# Schema_Arduino_Blinky.net
KiCad netlist of a schematic drawn in EAGLE
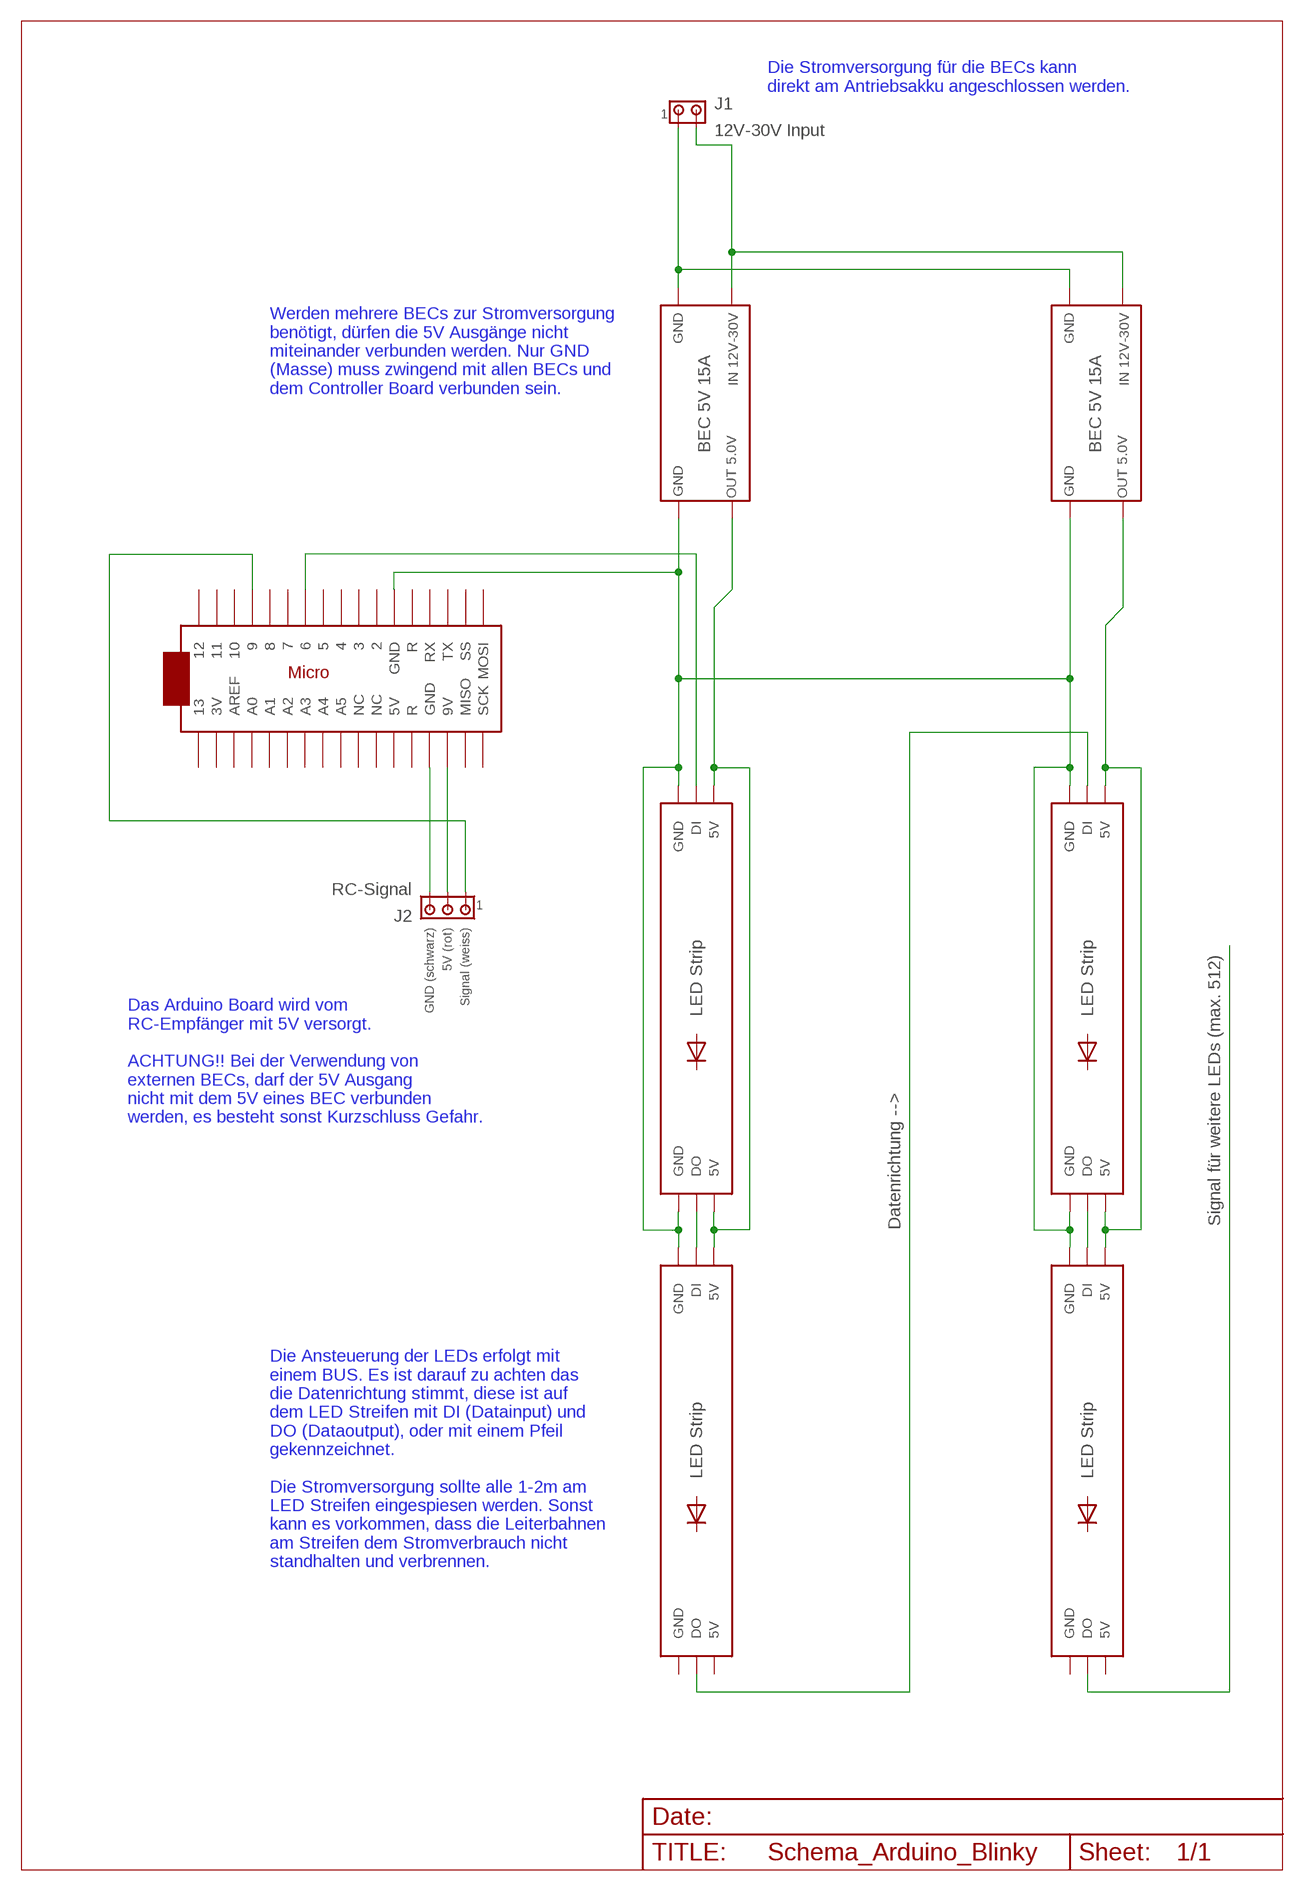
[diagram p0: schematic, sheet 1]

(export (version "E")
  (design (tool "Eeschema 10.0.6"))
  (components
    (comp (ref "J1")
      (value "12V-30V Input")
      (footprint "eagle-import:350428-1")
      (libsource (lib "eagle-import") (part "350428-1"))
    )
    (comp (ref "J2")
      (value "RC-Signal")
      (footprint "eagle-import:350429-1")
      (libsource (lib "eagle-import") (part "350429-1"))
    )
    (comp (ref "U$1")
      (value "ARDUINOMICRO")
      (footprint "eagle-import:ARDUINOMICRO")
      (libsource (lib "eagle-import") (part "ARDUINOMICRO"))
    )
  )
  (nets
    (net (code "1") (name "Net-(J2-Pad3)") (class "Default")
      (node (ref "J2") (pin "3") (pinfunction "3_3") (pintype "passive"))
      (node (ref "U$1") (pin "P$12") (pinfunction "GND_P$12") (pintype "bidirectional"))
    )
    (net (code "2") (name "Net-(U$1-9)") (class "Default")
      (node (ref "J2") (pin "1") (pinfunction "1_1") (pintype "passive"))
      (node (ref "U$1") (pin "P$4") (pinfunction "9_P$4") (pintype "bidirectional"))
    )
    (net (code "3") (name "Net-(U$1-9V)") (class "Default")
      (node (ref "J2") (pin "2") (pinfunction "2_2") (pintype "passive"))
      (node (ref "U$1") (pin "P$20") (pinfunction "9V_P$20") (pintype "bidirectional"))
    )
    (net (code "4") (name "unconnected-(J1-Pad1)") (class "Default")
      (node (ref "J1") (pin "1") (pinfunction "1_1") (pintype "passive"))
    )
    (net (code "5") (name "unconnected-(J1-Pad2)") (class "Default")
      (node (ref "J1") (pin "2") (pinfunction "2_2") (pintype "passive"))
    )
    (net (code "6") (name "unconnected-(U$1-2-PadP$11)") (class "Default")
      (node (ref "U$1") (pin "P$11") (pinfunction "2_P$11") (pintype "bidirectional"))
    )
    (net (code "7") (name "unconnected-(U$1-3-PadP$10)") (class "Default")
      (node (ref "U$1") (pin "P$10") (pinfunction "3_P$10") (pintype "bidirectional"))
    )
    (net (code "8") (name "unconnected-(U$1-3V-PadP$33)") (class "Default")
      (node (ref "U$1") (pin "P$33") (pinfunction "3V_P$33") (pintype "bidirectional"))
    )
    (net (code "9") (name "unconnected-(U$1-4-PadP$9)") (class "Default")
      (node (ref "U$1") (pin "P$9") (pinfunction "4_P$9") (pintype "bidirectional"))
    )
    (net (code "10") (name "unconnected-(U$1-5-PadP$8)") (class "Default")
      (node (ref "U$1") (pin "P$8") (pinfunction "5_P$8") (pintype "bidirectional"))
    )
    (net (code "11") (name "unconnected-(U$1-5V-PadP$23)") (class "Default")
      (node (ref "U$1") (pin "P$23") (pinfunction "5V_P$23") (pintype "bidirectional"))
    )
    (net (code "12") (name "unconnected-(U$1-6-PadP$7)") (class "Default")
      (node (ref "U$1") (pin "P$7") (pinfunction "6_P$7") (pintype "bidirectional"))
    )
    (net (code "13") (name "unconnected-(U$1-7-PadP$6)") (class "Default")
      (node (ref "U$1") (pin "P$6") (pinfunction "7_P$6") (pintype "bidirectional"))
    )
    (net (code "14") (name "unconnected-(U$1-8-PadP$5)") (class "Default")
      (node (ref "U$1") (pin "P$5") (pinfunction "8_P$5") (pintype "bidirectional"))
    )
    (net (code "15") (name "unconnected-(U$1-10-PadP$3)") (class "Default")
      (node (ref "U$1") (pin "P$3") (pinfunction "10_P$3") (pintype "bidirectional"))
    )
    (net (code "16") (name "unconnected-(U$1-11-PadP$2)") (class "Default")
      (node (ref "U$1") (pin "P$2") (pinfunction "11_P$2") (pintype "bidirectional"))
    )
    (net (code "17") (name "unconnected-(U$1-12-PadP$1)") (class "Default")
      (node (ref "U$1") (pin "P$1") (pinfunction "12_P$1") (pintype "bidirectional"))
    )
    (net (code "18") (name "unconnected-(U$1-13-PadP$34)") (class "Default")
      (node (ref "U$1") (pin "P$34") (pinfunction "13_P$34") (pintype "bidirectional"))
    )
    (net (code "19") (name "unconnected-(U$1-A0-PadP$31)") (class "Default")
      (node (ref "U$1") (pin "P$31") (pinfunction "A0_P$31") (pintype "bidirectional"))
    )
    (net (code "20") (name "unconnected-(U$1-A1-PadP$30)") (class "Default")
      (node (ref "U$1") (pin "P$30") (pinfunction "A1_P$30") (pintype "bidirectional"))
    )
    (net (code "21") (name "unconnected-(U$1-A2-PadP$29)") (class "Default")
      (node (ref "U$1") (pin "P$29") (pinfunction "A2_P$29") (pintype "bidirectional"))
    )
    (net (code "22") (name "unconnected-(U$1-A3-PadP$28)") (class "Default")
      (node (ref "U$1") (pin "P$28") (pinfunction "A3_P$28") (pintype "bidirectional"))
    )
    (net (code "23") (name "unconnected-(U$1-A4-PadP$27)") (class "Default")
      (node (ref "U$1") (pin "P$27") (pinfunction "A4_P$27") (pintype "bidirectional"))
    )
    (net (code "24") (name "unconnected-(U$1-A5-PadP$26)") (class "Default")
      (node (ref "U$1") (pin "P$26") (pinfunction "A5_P$26") (pintype "bidirectional"))
    )
    (net (code "25") (name "unconnected-(U$1-AREF-PadP$32)") (class "Default")
      (node (ref "U$1") (pin "P$32") (pinfunction "AREF_P$32") (pintype "bidirectional"))
    )
    (net (code "26") (name "unconnected-(U$1-GND-PadP$21)") (class "Default")
      (node (ref "U$1") (pin "P$21") (pinfunction "GND_P$21") (pintype "bidirectional"))
    )
    (net (code "27") (name "unconnected-(U$1-MISO-PadP$19)") (class "Default")
      (node (ref "U$1") (pin "P$19") (pinfunction "MISO_P$19") (pintype "bidirectional"))
    )
    (net (code "28") (name "unconnected-(U$1-MOSI-PadP$17)") (class "Default")
      (node (ref "U$1") (pin "P$17") (pinfunction "MOSI_P$17") (pintype "bidirectional"))
    )
    (net (code "29") (name "unconnected-(U$1-NC-PadP$24)") (class "Default")
      (node (ref "U$1") (pin "P$24") (pinfunction "NC_P$24") (pintype "bidirectional"))
    )
    (net (code "30") (name "unconnected-(U$1-NC-PadP$25)") (class "Default")
      (node (ref "U$1") (pin "P$25") (pinfunction "NC_P$25") (pintype "bidirectional"))
    )
    (net (code "31") (name "unconnected-(U$1-R-PadP$13)") (class "Default")
      (node (ref "U$1") (pin "P$13") (pinfunction "R_P$13") (pintype "bidirectional"))
    )
    (net (code "32") (name "unconnected-(U$1-R-PadP$22)") (class "Default")
      (node (ref "U$1") (pin "P$22") (pinfunction "R_P$22") (pintype "bidirectional"))
    )
    (net (code "33") (name "unconnected-(U$1-RX-PadP$14)") (class "Default")
      (node (ref "U$1") (pin "P$14") (pinfunction "RX_P$14") (pintype "bidirectional"))
    )
    (net (code "34") (name "unconnected-(U$1-SCK-PadP$18)") (class "Default")
      (node (ref "U$1") (pin "P$18") (pinfunction "SCK_P$18") (pintype "bidirectional"))
    )
    (net (code "35") (name "unconnected-(U$1-SS-PadP$16)") (class "Default")
      (node (ref "U$1") (pin "P$16") (pinfunction "SS_P$16") (pintype "bidirectional"))
    )
    (net (code "36") (name "unconnected-(U$1-TX-PadP$15)") (class "Default")
      (node (ref "U$1") (pin "P$15") (pinfunction "TX_P$15") (pintype "bidirectional"))
    )
  )
)
